# 8_button_harvester.net
KiCad netlist of a schematic drawn in EAGLE
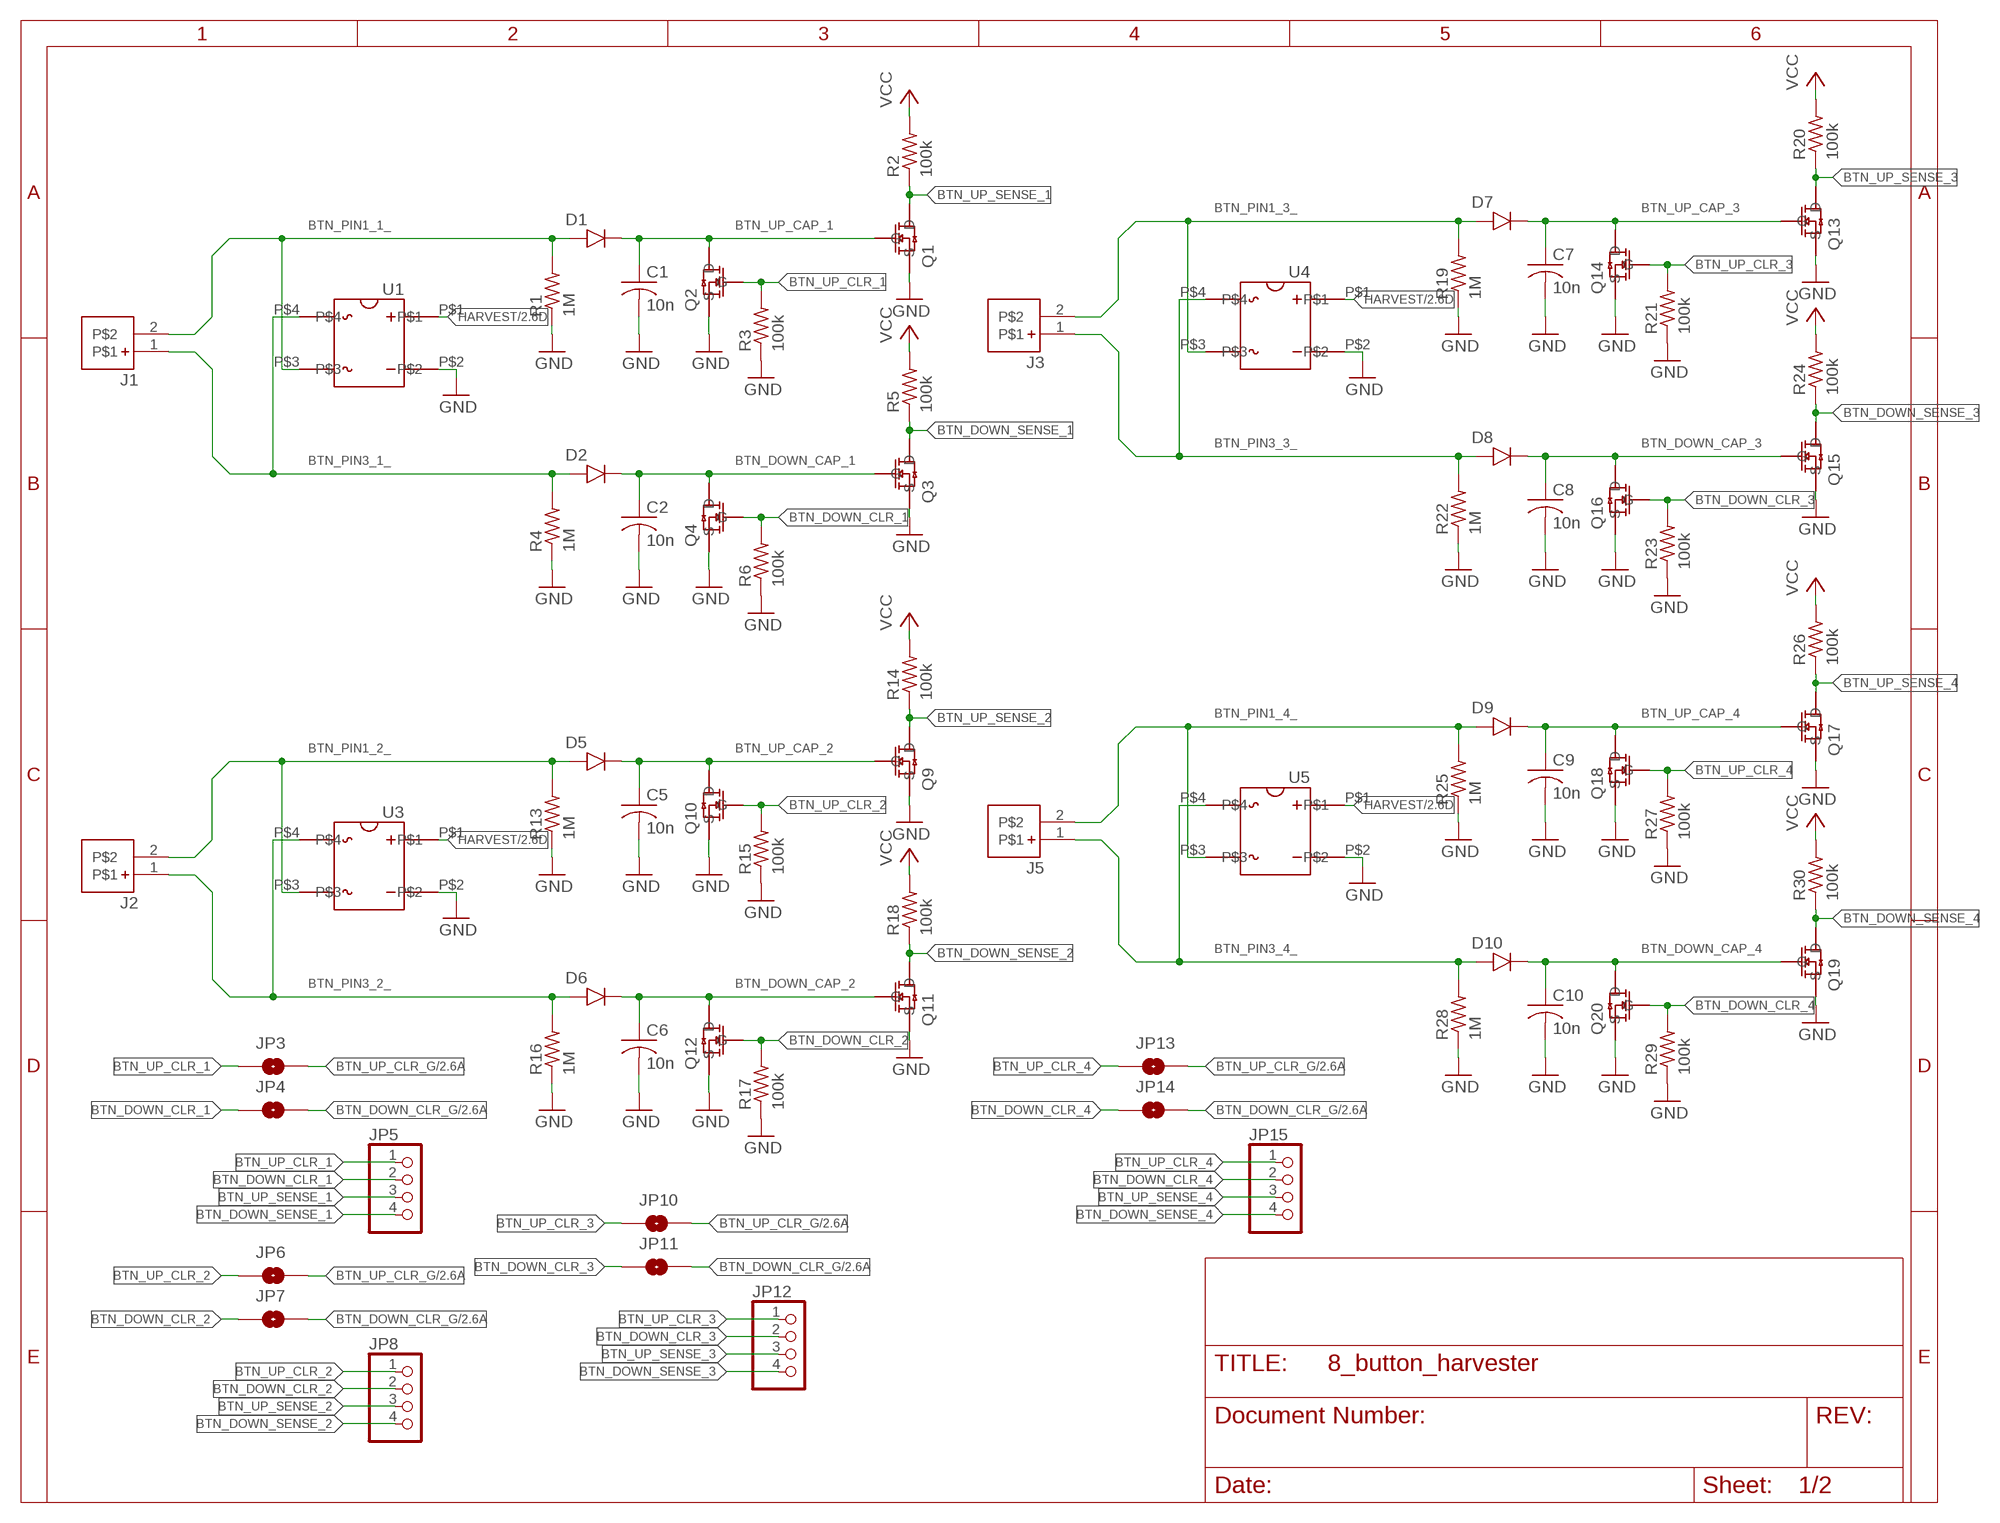
[diagram p0: schematic, sheet 1]
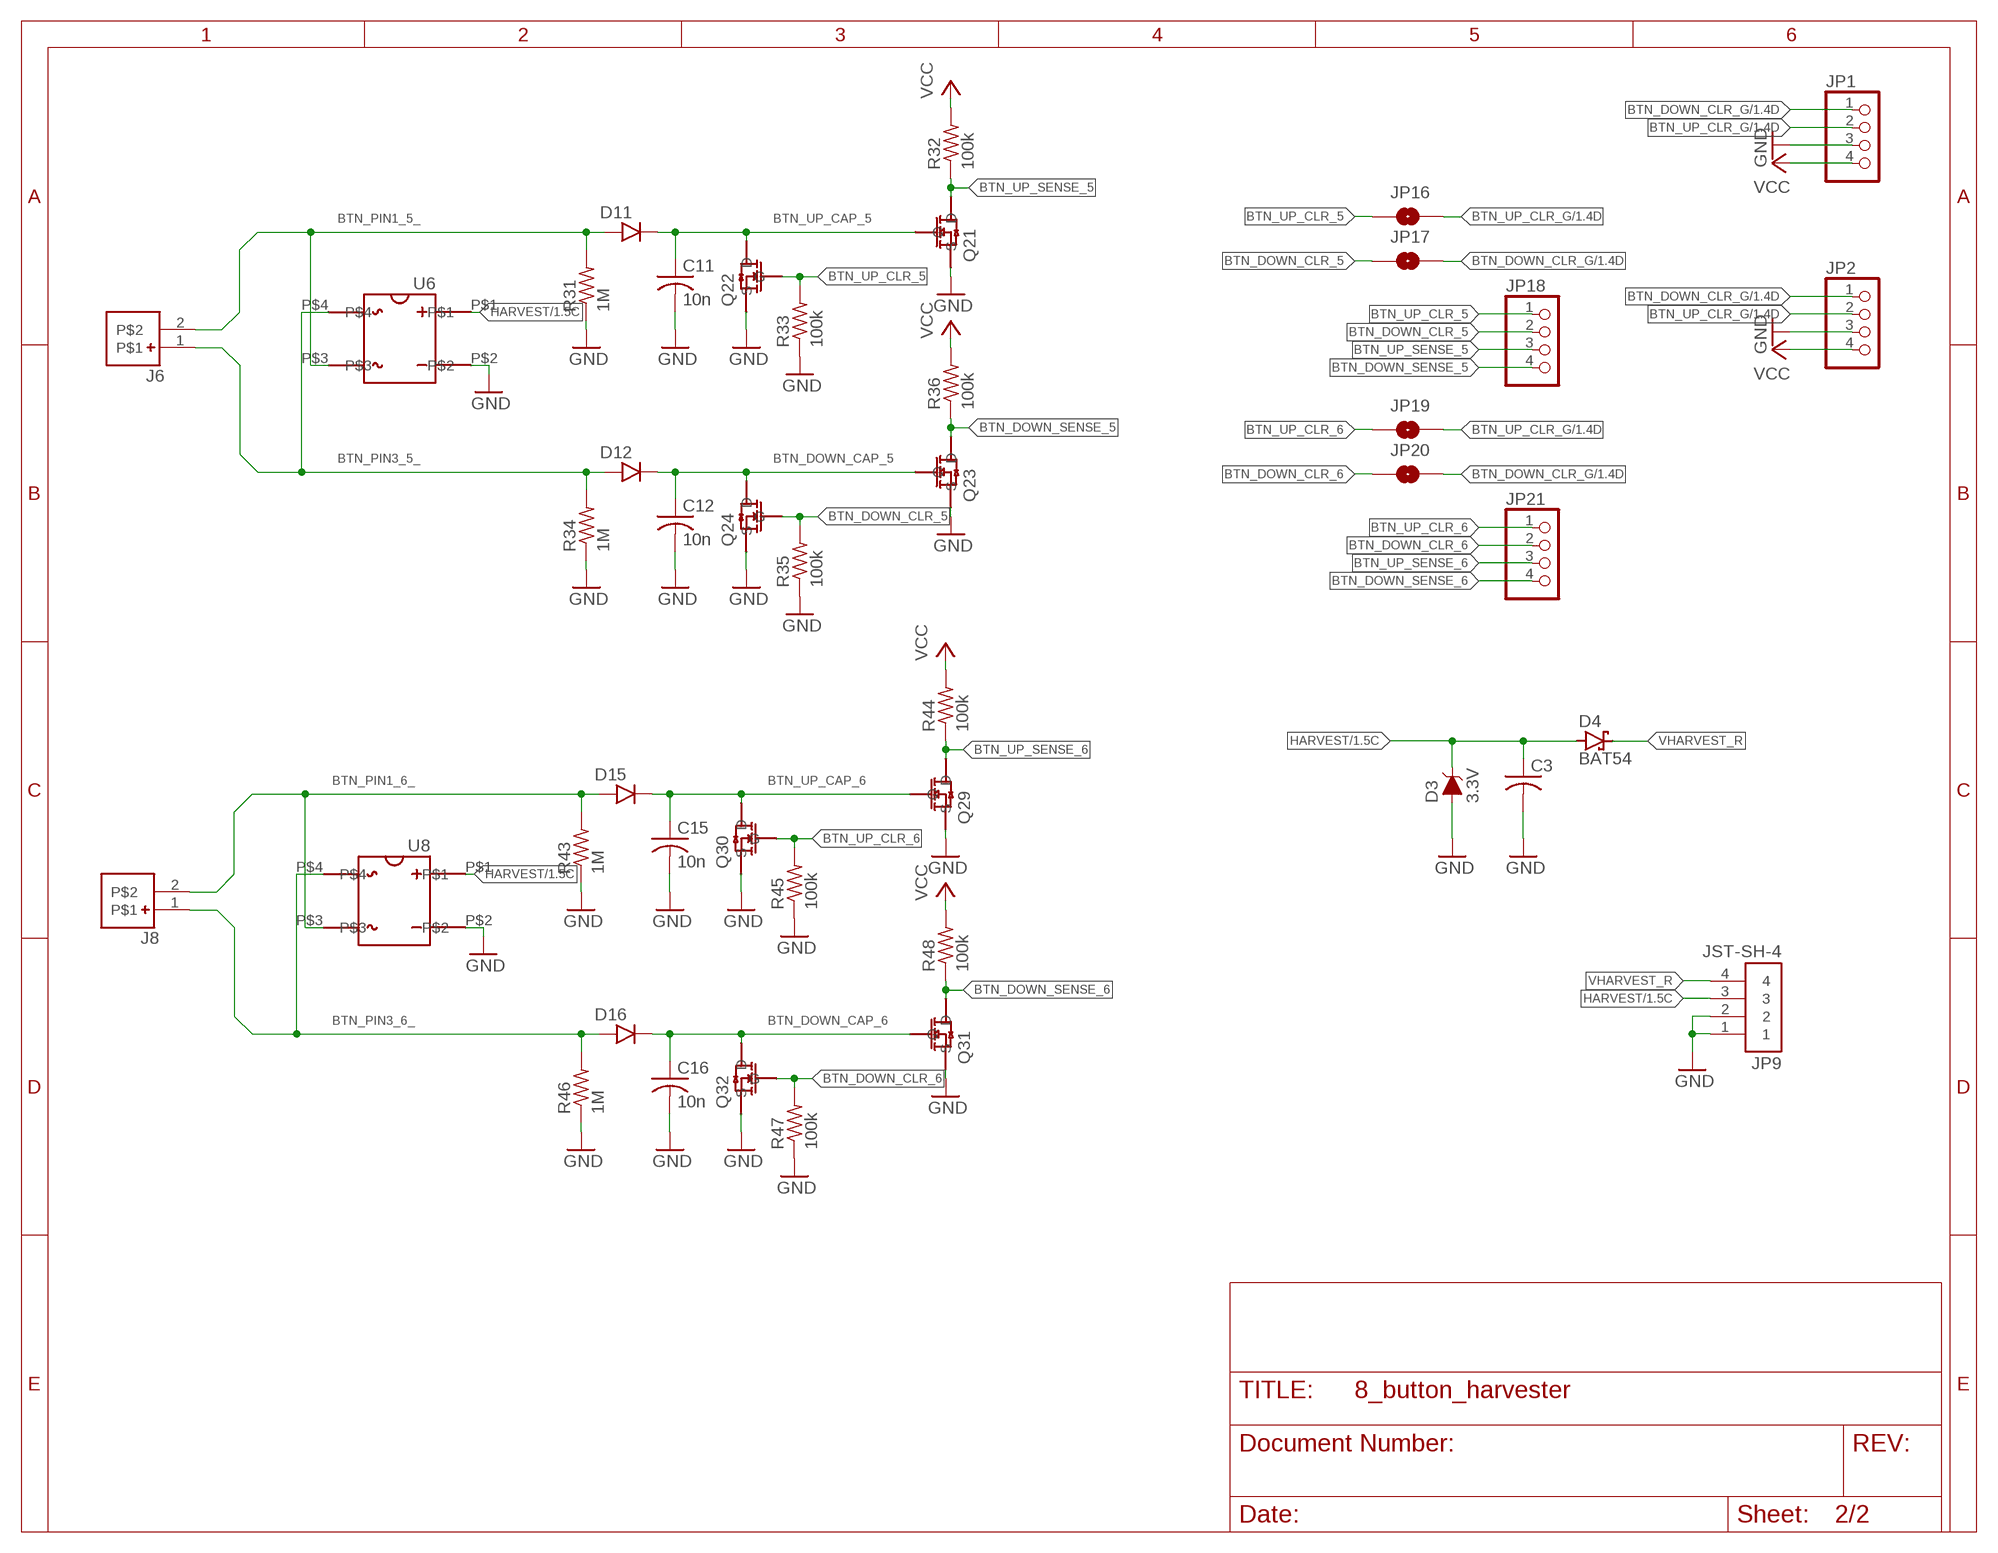
[diagram p1: schematic, sheet 2]

(export (version "E")
  (design (tool "Eeschema 10.0.6"))
  (components
    (comp (ref "C3")
      (value "C-USC0805")
      (footprint "eagle-import:C0805")
      (libsource (lib "eagle-import") (part "C-USC0805"))
    )
    (comp (ref "C11")
      (value "10n")
      (footprint "eagle-import:C0402")
      (libsource (lib "eagle-import") (part "C-USC0402"))
    )
    (comp (ref "C12")
      (value "10n")
      (footprint "eagle-import:C0402")
      (libsource (lib "eagle-import") (part "C-USC0402"))
    )
    (comp (ref "C15")
      (value "10n")
      (footprint "eagle-import:C0402")
      (libsource (lib "eagle-import") (part "C-USC0402"))
    )
    (comp (ref "C16")
      (value "10n")
      (footprint "eagle-import:C0402")
      (libsource (lib "eagle-import") (part "C-USC0402"))
    )
    (comp (ref "D3")
      (value "3.3V")
      (footprint "eagle-import:SOD-323")
      (libsource (lib "eagle-import") (part "DIODE-ZENER-MM3Z3V3T1G"))
    )
    (comp (ref "D4")
      (value "BAT54")
      (footprint "eagle-import:SOT23")
      (libsource (lib "eagle-import") (part "BAT54"))
    )
    (comp (ref "D11")
      (value "DFLU1200")
      (footprint "eagle-import:DFLU1200")
      (libsource (lib "eagle-import") (part "DFLU1200"))
    )
    (comp (ref "D12")
      (value "DFLU1200")
      (footprint "eagle-import:DFLU1200")
      (libsource (lib "eagle-import") (part "DFLU1200"))
    )
    (comp (ref "D15")
      (value "DFLU1200")
      (footprint "eagle-import:DFLU1200")
      (libsource (lib "eagle-import") (part "DFLU1200"))
    )
    (comp (ref "D16")
      (value "DFLU1200")
      (footprint "eagle-import:DFLU1200")
      (libsource (lib "eagle-import") (part "DFLU1200"))
    )
    (comp (ref "J6")
      (value "S2B-PH-SM4-TB")
      (footprint "eagle-import:S2B-PH-SM4-TB")
      (libsource (lib "eagle-import") (part "S2B-PH-SM4-TB"))
    )
    (comp (ref "J8")
      (value "S2B-PH-SM4-TB")
      (footprint "eagle-import:S2B-PH-SM4-TB")
      (libsource (lib "eagle-import") (part "S2B-PH-SM4-TB"))
    )
    (comp (ref "JP1")
      (value "PINHD-1X4")
      (footprint "eagle-import:1X04")
      (libsource (lib "eagle-import") (part "PINHD-1X4"))
    )
    (comp (ref "JP2")
      (value "PINHD-1X4")
      (footprint "eagle-import:1X04")
      (libsource (lib "eagle-import") (part "PINHD-1X4"))
    )
    (comp (ref "JP9")
      (value "JST-SH-4")
      (footprint "eagle-import:JST-SH-4")
      (libsource (lib "eagle-import") (part "JST-SH-4"))
    )
    (comp (ref "JP16")
      (value "JUMPER-SMT_2_NO_NO-SILK")
      (footprint "eagle-import:SMT-JUMPER_2_NO_NO-SILK")
      (libsource (lib "eagle-import") (part "JUMPER-SMT_2_NO_NO-SILK"))
    )
    (comp (ref "JP17")
      (value "JUMPER-SMT_2_NO_NO-SILK")
      (footprint "eagle-import:SMT-JUMPER_2_NO_NO-SILK")
      (libsource (lib "eagle-import") (part "JUMPER-SMT_2_NO_NO-SILK"))
    )
    (comp (ref "JP18")
      (value "PINHD-1X4")
      (footprint "eagle-import:1X04")
      (libsource (lib "eagle-import") (part "PINHD-1X4"))
    )
    (comp (ref "JP19")
      (value "JUMPER-SMT_2_NO_NO-SILK")
      (footprint "eagle-import:SMT-JUMPER_2_NO_NO-SILK")
      (libsource (lib "eagle-import") (part "JUMPER-SMT_2_NO_NO-SILK"))
    )
    (comp (ref "JP20")
      (value "JUMPER-SMT_2_NO_NO-SILK")
      (footprint "eagle-import:SMT-JUMPER_2_NO_NO-SILK")
      (libsource (lib "eagle-import") (part "JUMPER-SMT_2_NO_NO-SILK"))
    )
    (comp (ref "JP21")
      (value "PINHD-1X4")
      (footprint "eagle-import:1X04")
      (libsource (lib "eagle-import") (part "PINHD-1X4"))
    )
    (comp (ref "Q21")
      (value "2N7002K-7")
      (footprint "eagle-import:2N7002K-7")
      (libsource (lib "eagle-import") (part "2N7002K-7"))
    )
    (comp (ref "Q22")
      (value "BSS138K")
      (footprint "eagle-import:BSS138K")
      (libsource (lib "eagle-import") (part "BSS138K"))
    )
    (comp (ref "Q23")
      (value "2N7002K-7")
      (footprint "eagle-import:2N7002K-7")
      (libsource (lib "eagle-import") (part "2N7002K-7"))
    )
    (comp (ref "Q24")
      (value "BSS138K")
      (footprint "eagle-import:BSS138K")
      (libsource (lib "eagle-import") (part "BSS138K"))
    )
    (comp (ref "Q29")
      (value "2N7002K-7")
      (footprint "eagle-import:2N7002K-7")
      (libsource (lib "eagle-import") (part "2N7002K-7"))
    )
    (comp (ref "Q30")
      (value "BSS138K")
      (footprint "eagle-import:BSS138K")
      (libsource (lib "eagle-import") (part "BSS138K"))
    )
    (comp (ref "Q31")
      (value "2N7002K-7")
      (footprint "eagle-import:2N7002K-7")
      (libsource (lib "eagle-import") (part "2N7002K-7"))
    )
    (comp (ref "Q32")
      (value "BSS138K")
      (footprint "eagle-import:BSS138K")
      (libsource (lib "eagle-import") (part "BSS138K"))
    )
    (comp (ref "R31")
      (value "1M")
      (footprint "eagle-import:R0402")
      (libsource (lib "eagle-import") (part "R-US_R0402"))
    )
    (comp (ref "R32")
      (value "100k")
      (footprint "eagle-import:R0402")
      (libsource (lib "eagle-import") (part "R-US_R0402"))
    )
    (comp (ref "R33")
      (value "100k")
      (footprint "eagle-import:R0402")
      (libsource (lib "eagle-import") (part "R-US_R0402"))
    )
    (comp (ref "R34")
      (value "1M")
      (footprint "eagle-import:R0402")
      (libsource (lib "eagle-import") (part "R-US_R0402"))
    )
    (comp (ref "R35")
      (value "100k")
      (footprint "eagle-import:R0402")
      (libsource (lib "eagle-import") (part "R-US_R0402"))
    )
    (comp (ref "R36")
      (value "100k")
      (footprint "eagle-import:R0402")
      (libsource (lib "eagle-import") (part "R-US_R0402"))
    )
    (comp (ref "R43")
      (value "1M")
      (footprint "eagle-import:R0402")
      (libsource (lib "eagle-import") (part "R-US_R0402"))
    )
    (comp (ref "R44")
      (value "100k")
      (footprint "eagle-import:R0402")
      (libsource (lib "eagle-import") (part "R-US_R0402"))
    )
    (comp (ref "R45")
      (value "100k")
      (footprint "eagle-import:R0402")
      (libsource (lib "eagle-import") (part "R-US_R0402"))
    )
    (comp (ref "R46")
      (value "1M")
      (footprint "eagle-import:R0402")
      (libsource (lib "eagle-import") (part "R-US_R0402"))
    )
    (comp (ref "R47")
      (value "100k")
      (footprint "eagle-import:R0402")
      (libsource (lib "eagle-import") (part "R-US_R0402"))
    )
    (comp (ref "R48")
      (value "100k")
      (footprint "eagle-import:R0402")
      (libsource (lib "eagle-import") (part "R-US_R0402"))
    )
    (comp (ref "U6")
      (value "CDBHD140L-G")
      (footprint "eagle-import:CDBHDXX0L-G")
      (libsource (lib "eagle-import") (part "CDBHD140L-G"))
    )
    (comp (ref "U8")
      (value "CDBHD140L-G")
      (footprint "eagle-import:CDBHDXX0L-G")
      (libsource (lib "eagle-import") (part "CDBHD140L-G"))
    )
    (comp (ref "C1")
      (value "10n")
      (footprint "eagle-import:C0402")
      (libsource (lib "eagle-import") (part "C-USC0402"))
    )
    (comp (ref "C2")
      (value "10n")
      (footprint "eagle-import:C0402")
      (libsource (lib "eagle-import") (part "C-USC0402"))
    )
    (comp (ref "C5")
      (value "10n")
      (footprint "eagle-import:C0402")
      (libsource (lib "eagle-import") (part "C-USC0402"))
    )
    (comp (ref "C6")
      (value "10n")
      (footprint "eagle-import:C0402")
      (libsource (lib "eagle-import") (part "C-USC0402"))
    )
    (comp (ref "C7")
      (value "10n")
      (footprint "eagle-import:C0402")
      (libsource (lib "eagle-import") (part "C-USC0402"))
    )
    (comp (ref "C8")
      (value "10n")
      (footprint "eagle-import:C0402")
      (libsource (lib "eagle-import") (part "C-USC0402"))
    )
    (comp (ref "C9")
      (value "10n")
      (footprint "eagle-import:C0402")
      (libsource (lib "eagle-import") (part "C-USC0402"))
    )
    (comp (ref "C10")
      (value "10n")
      (footprint "eagle-import:C0402")
      (libsource (lib "eagle-import") (part "C-USC0402"))
    )
    (comp (ref "D1")
      (value "DFLU1200")
      (footprint "eagle-import:DFLU1200")
      (libsource (lib "eagle-import") (part "DFLU1200"))
    )
    (comp (ref "D2")
      (value "DFLU1200")
      (footprint "eagle-import:DFLU1200")
      (libsource (lib "eagle-import") (part "DFLU1200"))
    )
    (comp (ref "D5")
      (value "DFLU1200")
      (footprint "eagle-import:DFLU1200")
      (libsource (lib "eagle-import") (part "DFLU1200"))
    )
    (comp (ref "D6")
      (value "DFLU1200")
      (footprint "eagle-import:DFLU1200")
      (libsource (lib "eagle-import") (part "DFLU1200"))
    )
    (comp (ref "D7")
      (value "DFLU1200")
      (footprint "eagle-import:DFLU1200")
      (libsource (lib "eagle-import") (part "DFLU1200"))
    )
    (comp (ref "D8")
      (value "DFLU1200")
      (footprint "eagle-import:DFLU1200")
      (libsource (lib "eagle-import") (part "DFLU1200"))
    )
    (comp (ref "D9")
      (value "DFLU1200")
      (footprint "eagle-import:DFLU1200")
      (libsource (lib "eagle-import") (part "DFLU1200"))
    )
    (comp (ref "D10")
      (value "DFLU1200")
      (footprint "eagle-import:DFLU1200")
      (libsource (lib "eagle-import") (part "DFLU1200"))
    )
    (comp (ref "J1")
      (value "S2B-PH-SM4-TB")
      (footprint "eagle-import:S2B-PH-SM4-TB")
      (libsource (lib "eagle-import") (part "S2B-PH-SM4-TB"))
    )
    (comp (ref "J2")
      (value "S2B-PH-SM4-TB")
      (footprint "eagle-import:S2B-PH-SM4-TB")
      (libsource (lib "eagle-import") (part "S2B-PH-SM4-TB"))
    )
    (comp (ref "J3")
      (value "S2B-PH-SM4-TB")
      (footprint "eagle-import:S2B-PH-SM4-TB")
      (libsource (lib "eagle-import") (part "S2B-PH-SM4-TB"))
    )
    (comp (ref "J5")
      (value "S2B-PH-SM4-TB")
      (footprint "eagle-import:S2B-PH-SM4-TB")
      (libsource (lib "eagle-import") (part "S2B-PH-SM4-TB"))
    )
    (comp (ref "JP3")
      (value "JUMPER-SMT_2_NO_NO-SILK")
      (footprint "eagle-import:SMT-JUMPER_2_NO_NO-SILK")
      (libsource (lib "eagle-import") (part "JUMPER-SMT_2_NO_NO-SILK"))
    )
    (comp (ref "JP4")
      (value "JUMPER-SMT_2_NO_NO-SILK")
      (footprint "eagle-import:SMT-JUMPER_2_NO_NO-SILK")
      (libsource (lib "eagle-import") (part "JUMPER-SMT_2_NO_NO-SILK"))
    )
    (comp (ref "JP5")
      (value "PINHD-1X4")
      (footprint "eagle-import:1X04")
      (libsource (lib "eagle-import") (part "PINHD-1X4"))
    )
    (comp (ref "JP6")
      (value "JUMPER-SMT_2_NO_NO-SILK")
      (footprint "eagle-import:SMT-JUMPER_2_NO_NO-SILK")
      (libsource (lib "eagle-import") (part "JUMPER-SMT_2_NO_NO-SILK"))
    )
    (comp (ref "JP7")
      (value "JUMPER-SMT_2_NO_NO-SILK")
      (footprint "eagle-import:SMT-JUMPER_2_NO_NO-SILK")
      (libsource (lib "eagle-import") (part "JUMPER-SMT_2_NO_NO-SILK"))
    )
    (comp (ref "JP8")
      (value "PINHD-1X4")
      (footprint "eagle-import:1X04")
      (libsource (lib "eagle-import") (part "PINHD-1X4"))
    )
    (comp (ref "JP10")
      (value "JUMPER-SMT_2_NO_NO-SILK")
      (footprint "eagle-import:SMT-JUMPER_2_NO_NO-SILK")
      (libsource (lib "eagle-import") (part "JUMPER-SMT_2_NO_NO-SILK"))
    )
    (comp (ref "JP11")
      (value "JUMPER-SMT_2_NO_NO-SILK")
      (footprint "eagle-import:SMT-JUMPER_2_NO_NO-SILK")
      (libsource (lib "eagle-import") (part "JUMPER-SMT_2_NO_NO-SILK"))
    )
    (comp (ref "JP12")
      (value "PINHD-1X4")
      (footprint "eagle-import:1X04")
      (libsource (lib "eagle-import") (part "PINHD-1X4"))
    )
    (comp (ref "JP13")
      (value "JUMPER-SMT_2_NO_NO-SILK")
      (footprint "eagle-import:SMT-JUMPER_2_NO_NO-SILK")
      (libsource (lib "eagle-import") (part "JUMPER-SMT_2_NO_NO-SILK"))
    )
    (comp (ref "JP14")
      (value "JUMPER-SMT_2_NO_NO-SILK")
      (footprint "eagle-import:SMT-JUMPER_2_NO_NO-SILK")
      (libsource (lib "eagle-import") (part "JUMPER-SMT_2_NO_NO-SILK"))
    )
    (comp (ref "JP15")
      (value "PINHD-1X4")
      (footprint "eagle-import:1X04")
      (libsource (lib "eagle-import") (part "PINHD-1X4"))
    )
    (comp (ref "Q1")
      (value "2N7002K-7")
      (footprint "eagle-import:2N7002K-7")
      (libsource (lib "eagle-import") (part "2N7002K-7"))
    )
    (comp (ref "Q2")
      (value "BSS138K")
      (footprint "eagle-import:BSS138K")
      (libsource (lib "eagle-import") (part "BSS138K"))
    )
    (comp (ref "Q3")
      (value "2N7002K-7")
      (footprint "eagle-import:2N7002K-7")
      (libsource (lib "eagle-import") (part "2N7002K-7"))
    )
    (comp (ref "Q4")
      (value "BSS138K")
      (footprint "eagle-import:BSS138K")
      (libsource (lib "eagle-import") (part "BSS138K"))
    )
    (comp (ref "Q9")
      (value "2N7002K-7")
      (footprint "eagle-import:2N7002K-7")
      (libsource (lib "eagle-import") (part "2N7002K-7"))
    )
    (comp (ref "Q10")
      (value "BSS138K")
      (footprint "eagle-import:BSS138K")
      (libsource (lib "eagle-import") (part "BSS138K"))
    )
    (comp (ref "Q11")
      (value "2N7002K-7")
      (footprint "eagle-import:2N7002K-7")
      (libsource (lib "eagle-import") (part "2N7002K-7"))
    )
    (comp (ref "Q12")
      (value "BSS138K")
      (footprint "eagle-import:BSS138K")
      (libsource (lib "eagle-import") (part "BSS138K"))
    )
    (comp (ref "Q13")
      (value "2N7002K-7")
      (footprint "eagle-import:2N7002K-7")
      (libsource (lib "eagle-import") (part "2N7002K-7"))
    )
    (comp (ref "Q14")
      (value "BSS138K")
      (footprint "eagle-import:BSS138K")
      (libsource (lib "eagle-import") (part "BSS138K"))
    )
    (comp (ref "Q15")
      (value "2N7002K-7")
      (footprint "eagle-import:2N7002K-7")
      (libsource (lib "eagle-import") (part "2N7002K-7"))
    )
    (comp (ref "Q16")
      (value "BSS138K")
      (footprint "eagle-import:BSS138K")
      (libsource (lib "eagle-import") (part "BSS138K"))
    )
    (comp (ref "Q17")
      (value "2N7002K-7")
      (footprint "eagle-import:2N7002K-7")
      (libsource (lib "eagle-import") (part "2N7002K-7"))
    )
    (comp (ref "Q18")
      (value "BSS138K")
      (footprint "eagle-import:BSS138K")
      (libsource (lib "eagle-import") (part "BSS138K"))
    )
    (comp (ref "Q19")
      (value "2N7002K-7")
      (footprint "eagle-import:2N7002K-7")
      (libsource (lib "eagle-import") (part "2N7002K-7"))
    )
    (comp (ref "Q20")
      (value "BSS138K")
      (footprint "eagle-import:BSS138K")
      (libsource (lib "eagle-import") (part "BSS138K"))
    )
    (comp (ref "R1")
      (value "1M")
      (footprint "eagle-import:R0402")
      (libsource (lib "eagle-import") (part "R-US_R0402"))
    )
    (comp (ref "R2")
      (value "100k")
      (footprint "eagle-import:R0402")
      (libsource (lib "eagle-import") (part "R-US_R0402"))
    )
    (comp (ref "R3")
      (value "100k")
      (footprint "eagle-import:R0402")
      (libsource (lib "eagle-import") (part "R-US_R0402"))
    )
    (comp (ref "R4")
      (value "1M")
      (footprint "eagle-import:R0402")
      (libsource (lib "eagle-import") (part "R-US_R0402"))
    )
    (comp (ref "R5")
      (value "100k")
      (footprint "eagle-import:R0402")
      (libsource (lib "eagle-import") (part "R-US_R0402"))
    )
    (comp (ref "R6")
      (value "100k")
      (footprint "eagle-import:R0402")
      (libsource (lib "eagle-import") (part "R-US_R0402"))
    )
    (comp (ref "R13")
      (value "1M")
      (footprint "eagle-import:R0402")
      (libsource (lib "eagle-import") (part "R-US_R0402"))
    )
    (comp (ref "R14")
      (value "100k")
      (footprint "eagle-import:R0402")
      (libsource (lib "eagle-import") (part "R-US_R0402"))
    )
    (comp (ref "R15")
      (value "100k")
      (footprint "eagle-import:R0402")
      (libsource (lib "eagle-import") (part "R-US_R0402"))
    )
    (comp (ref "R16")
      (value "1M")
      (footprint "eagle-import:R0402")
      (libsource (lib "eagle-import") (part "R-US_R0402"))
    )
    (comp (ref "R17")
      (value "100k")
      (footprint "eagle-import:R0402")
      (libsource (lib "eagle-import") (part "R-US_R0402"))
    )
    (comp (ref "R18")
      (value "100k")
      (footprint "eagle-import:R0402")
      (libsource (lib "eagle-import") (part "R-US_R0402"))
    )
    (comp (ref "R19")
      (value "1M")
      (footprint "eagle-import:R0402")
      (libsource (lib "eagle-import") (part "R-US_R0402"))
    )
    (comp (ref "R20")
      (value "100k")
      (footprint "eagle-import:R0402")
      (libsource (lib "eagle-import") (part "R-US_R0402"))
    )
    (comp (ref "R21")
      (value "100k")
      (footprint "eagle-import:R0402")
      (libsource (lib "eagle-import") (part "R-US_R0402"))
    )
    (comp (ref "R22")
      (value "1M")
      (footprint "eagle-import:R0402")
      (libsource (lib "eagle-import") (part "R-US_R0402"))
    )
    (comp (ref "R23")
      (value "100k")
      (footprint "eagle-import:R0402")
      (libsource (lib "eagle-import") (part "R-US_R0402"))
    )
    (comp (ref "R24")
      (value "100k")
      (footprint "eagle-import:R0402")
      (libsource (lib "eagle-import") (part "R-US_R0402"))
    )
    (comp (ref "R25")
      (value "1M")
      (footprint "eagle-import:R0402")
      (libsource (lib "eagle-import") (part "R-US_R0402"))
    )
    (comp (ref "R26")
      (value "100k")
      (footprint "eagle-import:R0402")
      (libsource (lib "eagle-import") (part "R-US_R0402"))
    )
    (comp (ref "R27")
      (value "100k")
      (footprint "eagle-import:R0402")
      (libsource (lib "eagle-import") (part "R-US_R0402"))
    )
    (comp (ref "R28")
      (value "1M")
      (footprint "eagle-import:R0402")
      (libsource (lib "eagle-import") (part "R-US_R0402"))
    )
    (comp (ref "R29")
      (value "100k")
      (footprint "eagle-import:R0402")
      (libsource (lib "eagle-import") (part "R-US_R0402"))
    )
    (comp (ref "R30")
      (value "100k")
      (footprint "eagle-import:R0402")
      (libsource (lib "eagle-import") (part "R-US_R0402"))
    )
    (comp (ref "U1")
      (value "CDBHD140L-G")
      (footprint "eagle-import:CDBHDXX0L-G")
      (libsource (lib "eagle-import") (part "CDBHD140L-G"))
    )
    (comp (ref "U3")
      (value "CDBHD140L-G")
      (footprint "eagle-import:CDBHDXX0L-G")
      (libsource (lib "eagle-import") (part "CDBHD140L-G"))
    )
    (comp (ref "U4")
      (value "CDBHD140L-G")
      (footprint "eagle-import:CDBHDXX0L-G")
      (libsource (lib "eagle-import") (part "CDBHD140L-G"))
    )
    (comp (ref "U5")
      (value "CDBHD140L-G")
      (footprint "eagle-import:CDBHDXX0L-G")
      (libsource (lib "eagle-import") (part "CDBHD140L-G"))
    )
  )
  (nets
    (net (code "1") (name "BTN_DOWN_CAP_1") (class "Default")
      (node (ref "C2") (pin "1") (pinfunction "1_1") (pintype "passive"))
      (node (ref "D2") (pin "K") (pinfunction "K_K") (pintype "bidirectional"))
      (node (ref "Q3") (pin "G") (pinfunction "G_G") (pintype "bidirectional"))
      (node (ref "Q4") (pin "D") (pinfunction "D_D") (pintype "bidirectional"))
    )
    (net (code "2") (name "BTN_DOWN_CAP_2") (class "Default")
      (node (ref "C6") (pin "1") (pinfunction "1_1") (pintype "passive"))
      (node (ref "D6") (pin "K") (pinfunction "K_K") (pintype "bidirectional"))
      (node (ref "Q11") (pin "G") (pinfunction "G_G") (pintype "bidirectional"))
      (node (ref "Q12") (pin "D") (pinfunction "D_D") (pintype "bidirectional"))
    )
    (net (code "3") (name "BTN_DOWN_CAP_3") (class "Default")
      (node (ref "C8") (pin "1") (pinfunction "1_1") (pintype "passive"))
      (node (ref "D8") (pin "K") (pinfunction "K_K") (pintype "bidirectional"))
      (node (ref "Q15") (pin "G") (pinfunction "G_G") (pintype "bidirectional"))
      (node (ref "Q16") (pin "D") (pinfunction "D_D") (pintype "bidirectional"))
    )
    (net (code "4") (name "BTN_DOWN_CAP_4") (class "Default")
      (node (ref "C10") (pin "1") (pinfunction "1_1") (pintype "passive"))
      (node (ref "D10") (pin "K") (pinfunction "K_K") (pintype "bidirectional"))
      (node (ref "Q19") (pin "G") (pinfunction "G_G") (pintype "bidirectional"))
      (node (ref "Q20") (pin "D") (pinfunction "D_D") (pintype "bidirectional"))
    )
    (net (code "5") (name "BTN_DOWN_CAP_5") (class "Default")
      (node (ref "C12") (pin "1") (pinfunction "1_1") (pintype "passive"))
      (node (ref "D12") (pin "K") (pinfunction "K_K") (pintype "bidirectional"))
      (node (ref "Q23") (pin "G") (pinfunction "G_G") (pintype "bidirectional"))
      (node (ref "Q24") (pin "D") (pinfunction "D_D") (pintype "bidirectional"))
    )
    (net (code "6") (name "BTN_DOWN_CAP_6") (class "Default")
      (node (ref "C16") (pin "1") (pinfunction "1_1") (pintype "passive"))
      (node (ref "D16") (pin "K") (pinfunction "K_K") (pintype "bidirectional"))
      (node (ref "Q31") (pin "G") (pinfunction "G_G") (pintype "bidirectional"))
      (node (ref "Q32") (pin "D") (pinfunction "D_D") (pintype "bidirectional"))
    )
    (net (code "7") (name "BTN_DOWN_CLR_1") (class "Default")
      (node (ref "JP4") (pin "1") (pinfunction "1_1") (pintype "passive"))
      (node (ref "JP5") (pin "2") (pinfunction "2_2") (pintype "passive"))
      (node (ref "Q4") (pin "G") (pinfunction "G_G") (pintype "bidirectional"))
      (node (ref "R6") (pin "2") (pinfunction "2_2") (pintype "passive"))
    )
    (net (code "8") (name "BTN_DOWN_CLR_2") (class "Default")
      (node (ref "JP7") (pin "1") (pinfunction "1_1") (pintype "passive"))
      (node (ref "JP8") (pin "2") (pinfunction "2_2") (pintype "passive"))
      (node (ref "Q12") (pin "G") (pinfunction "G_G") (pintype "bidirectional"))
      (node (ref "R17") (pin "2") (pinfunction "2_2") (pintype "passive"))
    )
    (net (code "9") (name "BTN_DOWN_CLR_3") (class "Default")
      (node (ref "JP11") (pin "1") (pinfunction "1_1") (pintype "passive"))
      (node (ref "JP12") (pin "2") (pinfunction "2_2") (pintype "passive"))
      (node (ref "Q16") (pin "G") (pinfunction "G_G") (pintype "bidirectional"))
      (node (ref "R23") (pin "2") (pinfunction "2_2") (pintype "passive"))
    )
    (net (code "10") (name "BTN_DOWN_CLR_4") (class "Default")
      (node (ref "JP14") (pin "1") (pinfunction "1_1") (pintype "passive"))
      (node (ref "JP15") (pin "2") (pinfunction "2_2") (pintype "passive"))
      (node (ref "Q20") (pin "G") (pinfunction "G_G") (pintype "bidirectional"))
      (node (ref "R29") (pin "2") (pinfunction "2_2") (pintype "passive"))
    )
    (net (code "11") (name "BTN_DOWN_CLR_5") (class "Default")
      (node (ref "JP17") (pin "1") (pinfunction "1_1") (pintype "passive"))
      (node (ref "JP18") (pin "2") (pinfunction "2_2") (pintype "passive"))
      (node (ref "Q24") (pin "G") (pinfunction "G_G") (pintype "bidirectional"))
      (node (ref "R35") (pin "2") (pinfunction "2_2") (pintype "passive"))
    )
    (net (code "12") (name "BTN_DOWN_CLR_6") (class "Default")
      (node (ref "JP20") (pin "1") (pinfunction "1_1") (pintype "passive"))
      (node (ref "JP21") (pin "2") (pinfunction "2_2") (pintype "passive"))
      (node (ref "Q32") (pin "G") (pinfunction "G_G") (pintype "bidirectional"))
      (node (ref "R47") (pin "2") (pinfunction "2_2") (pintype "passive"))
    )
    (net (code "13") (name "BTN_DOWN_CLR_G") (class "Default")
      (node (ref "JP1") (pin "1") (pinfunction "1_1") (pintype "passive"))
      (node (ref "JP11") (pin "2") (pinfunction "2_2") (pintype "passive"))
      (node (ref "JP14") (pin "2") (pinfunction "2_2") (pintype "passive"))
      (node (ref "JP17") (pin "2") (pinfunction "2_2") (pintype "passive"))
      (node (ref "JP2") (pin "1") (pinfunction "1_1") (pintype "passive"))
      (node (ref "JP20") (pin "2") (pinfunction "2_2") (pintype "passive"))
      (node (ref "JP4") (pin "2") (pinfunction "2_2") (pintype "passive"))
      (node (ref "JP7") (pin "2") (pinfunction "2_2") (pintype "passive"))
    )
    (net (code "14") (name "BTN_DOWN_SENSE_1") (class "Default")
      (node (ref "JP5") (pin "4") (pinfunction "4_4") (pintype "passive"))
      (node (ref "Q3") (pin "D") (pinfunction "D_D") (pintype "bidirectional"))
      (node (ref "R5") (pin "1") (pinfunction "1_1") (pintype "passive"))
    )
    (net (code "15") (name "BTN_DOWN_SENSE_2") (class "Default")
      (node (ref "JP8") (pin "4") (pinfunction "4_4") (pintype "passive"))
      (node (ref "Q11") (pin "D") (pinfunction "D_D") (pintype "bidirectional"))
      (node (ref "R18") (pin "1") (pinfunction "1_1") (pintype "passive"))
    )
    (net (code "16") (name "BTN_DOWN_SENSE_3") (class "Default")
      (node (ref "JP12") (pin "4") (pinfunction "4_4") (pintype "passive"))
      (node (ref "Q15") (pin "D") (pinfunction "D_D") (pintype "bidirectional"))
      (node (ref "R24") (pin "1") (pinfunction "1_1") (pintype "passive"))
    )
    (net (code "17") (name "BTN_DOWN_SENSE_4") (class "Default")
      (node (ref "JP15") (pin "4") (pinfunction "4_4") (pintype "passive"))
      (node (ref "Q19") (pin "D") (pinfunction "D_D") (pintype "bidirectional"))
      (node (ref "R30") (pin "1") (pinfunction "1_1") (pintype "passive"))
    )
    (net (code "18") (name "BTN_DOWN_SENSE_5") (class "Default")
      (node (ref "JP18") (pin "4") (pinfunction "4_4") (pintype "passive"))
      (node (ref "Q23") (pin "D") (pinfunction "D_D") (pintype "bidirectional"))
      (node (ref "R36") (pin "1") (pinfunction "1_1") (pintype "passive"))
    )
    (net (code "19") (name "BTN_DOWN_SENSE_6") (class "Default")
      (node (ref "JP21") (pin "4") (pinfunction "4_4") (pintype "passive"))
      (node (ref "Q31") (pin "D") (pinfunction "D_D") (pintype "bidirectional"))
      (node (ref "R48") (pin "1") (pinfunction "1_1") (pintype "passive"))
    )
    (net (code "20") (name "BTN_PIN1_1_") (class "Default")
      (node (ref "D1") (pin "A") (pinfunction "A_A") (pintype "bidirectional"))
      (node (ref "J1") (pin "2") (pinfunction "P$2_2") (pintype "bidirectional"))
      (node (ref "R1") (pin "2") (pinfunction "2_2") (pintype "passive"))
      (node (ref "U1") (pin "P$3") (pinfunction "P$3_P$3") (pintype "bidirectional"))
    )
    (net (code "21") (name "BTN_PIN1_2_") (class "Default")
      (node (ref "D5") (pin "A") (pinfunction "A_A") (pintype "bidirectional"))
      (node (ref "J2") (pin "2") (pinfunction "P$2_2") (pintype "bidirectional"))
      (node (ref "R13") (pin "2") (pinfunction "2_2") (pintype "passive"))
      (node (ref "U3") (pin "P$3") (pinfunction "P$3_P$3") (pintype "bidirectional"))
    )
    (net (code "22") (name "BTN_PIN1_3_") (class "Default")
      (node (ref "D7") (pin "A") (pinfunction "A_A") (pintype "bidirectional"))
      (node (ref "J3") (pin "2") (pinfunction "P$2_2") (pintype "bidirectional"))
      (node (ref "R19") (pin "2") (pinfunction "2_2") (pintype "passive"))
      (node (ref "U4") (pin "P$3") (pinfunction "P$3_P$3") (pintype "bidirectional"))
    )
    (net (code "23") (name "BTN_PIN1_4_") (class "Default")
      (node (ref "D9") (pin "A") (pinfunction "A_A") (pintype "bidirectional"))
      (node (ref "J5") (pin "2") (pinfunction "P$2_2") (pintype "bidirectional"))
      (node (ref "R25") (pin "2") (pinfunction "2_2") (pintype "passive"))
      (node (ref "U5") (pin "P$3") (pinfunction "P$3_P$3") (pintype "bidirectional"))
    )
    (net (code "24") (name "BTN_PIN1_5_") (class "Default")
      (node (ref "D11") (pin "A") (pinfunction "A_A") (pintype "bidirectional"))
      (node (ref "J6") (pin "2") (pinfunction "P$2_2") (pintype "bidirectional"))
      (node (ref "R31") (pin "2") (pinfunction "2_2") (pintype "passive"))
      (node (ref "U6") (pin "P$3") (pinfunction "P$3_P$3") (pintype "bidirectional"))
    )
    (net (code "25") (name "BTN_PIN1_6_") (class "Default")
      (node (ref "D15") (pin "A") (pinfunction "A_A") (pintype "bidirectional"))
      (node (ref "J8") (pin "2") (pinfunction "P$2_2") (pintype "bidirectional"))
      (node (ref "R43") (pin "2") (pinfunction "2_2") (pintype "passive"))
      (node (ref "U8") (pin "P$3") (pinfunction "P$3_P$3") (pintype "bidirectional"))
    )
    (net (code "26") (name "BTN_PIN3_1_") (class "Default")
      (node (ref "D2") (pin "A") (pinfunction "A_A") (pintype "bidirectional"))
      (node (ref "J1") (pin "1") (pinfunction "P$1_1") (pintype "bidirectional"))
      (node (ref "R4") (pin "2") (pinfunction "2_2") (pintype "passive"))
      (node (ref "U1") (pin "P$4") (pinfunction "P$4_P$4") (pintype "bidirectional"))
    )
    (net (code "27") (name "BTN_PIN3_2_") (class "Default")
      (node (ref "D6") (pin "A") (pinfunction "A_A") (pintype "bidirectional"))
      (node (ref "J2") (pin "1") (pinfunction "P$1_1") (pintype "bidirectional"))
      (node (ref "R16") (pin "2") (pinfunction "2_2") (pintype "passive"))
      (node (ref "U3") (pin "P$4") (pinfunction "P$4_P$4") (pintype "bidirectional"))
    )
    (net (code "28") (name "BTN_PIN3_3_") (class "Default")
      (node (ref "D8") (pin "A") (pinfunction "A_A") (pintype "bidirectional"))
      (node (ref "J3") (pin "1") (pinfunction "P$1_1") (pintype "bidirectional"))
      (node (ref "R22") (pin "2") (pinfunction "2_2") (pintype "passive"))
      (node (ref "U4") (pin "P$4") (pinfunction "P$4_P$4") (pintype "bidirectional"))
    )
    (net (code "29") (name "BTN_PIN3_4_") (class "Default")
      (node (ref "D10") (pin "A") (pinfunction "A_A") (pintype "bidirectional"))
      (node (ref "J5") (pin "1") (pinfunction "P$1_1") (pintype "bidirectional"))
      (node (ref "R28") (pin "2") (pinfunction "2_2") (pintype "passive"))
      (node (ref "U5") (pin "P$4") (pinfunction "P$4_P$4") (pintype "bidirectional"))
    )
    (net (code "30") (name "BTN_PIN3_5_") (class "Default")
      (node (ref "D12") (pin "A") (pinfunction "A_A") (pintype "bidirectional"))
      (node (ref "J6") (pin "1") (pinfunction "P$1_1") (pintype "bidirectional"))
      (node (ref "R34") (pin "2") (pinfunction "2_2") (pintype "passive"))
      (node (ref "U6") (pin "P$4") (pinfunction "P$4_P$4") (pintype "bidirectional"))
    )
    (net (code "31") (name "BTN_PIN3_6_") (class "Default")
      (node (ref "D16") (pin "A") (pinfunction "A_A") (pintype "bidirectional"))
      (node (ref "J8") (pin "1") (pinfunction "P$1_1") (pintype "bidirectional"))
      (node (ref "R46") (pin "2") (pinfunction "2_2") (pintype "passive"))
      (node (ref "U8") (pin "P$4") (pinfunction "P$4_P$4") (pintype "bidirectional"))
    )
    (net (code "32") (name "BTN_UP_CAP_1") (class "Default")
      (node (ref "C1") (pin "1") (pinfunction "1_1") (pintype "passive"))
      (node (ref "D1") (pin "K") (pinfunction "K_K") (pintype "bidirectional"))
      (node (ref "Q1") (pin "G") (pinfunction "G_G") (pintype "bidirectional"))
      (node (ref "Q2") (pin "D") (pinfunction "D_D") (pintype "bidirectional"))
    )
    (net (code "33") (name "BTN_UP_CAP_2") (class "Default")
      (node (ref "C5") (pin "1") (pinfunction "1_1") (pintype "passive"))
      (node (ref "D5") (pin "K") (pinfunction "K_K") (pintype "bidirectional"))
      (node (ref "Q10") (pin "D") (pinfunction "D_D") (pintype "bidirectional"))
      (node (ref "Q9") (pin "G") (pinfunction "G_G") (pintype "bidirectional"))
    )
    (net (code "34") (name "BTN_UP_CAP_3") (class "Default")
      (node (ref "C7") (pin "1") (pinfunction "1_1") (pintype "passive"))
      (node (ref "D7") (pin "K") (pinfunction "K_K") (pintype "bidirectional"))
      (node (ref "Q13") (pin "G") (pinfunction "G_G") (pintype "bidirectional"))
      (node (ref "Q14") (pin "D") (pinfunction "D_D") (pintype "bidirectional"))
    )
    (net (code "35") (name "BTN_UP_CAP_4") (class "Default")
      (node (ref "C9") (pin "1") (pinfunction "1_1") (pintype "passive"))
      (node (ref "D9") (pin "K") (pinfunction "K_K") (pintype "bidirectional"))
      (node (ref "Q17") (pin "G") (pinfunction "G_G") (pintype "bidirectional"))
      (node (ref "Q18") (pin "D") (pinfunction "D_D") (pintype "bidirectional"))
    )
    (net (code "36") (name "BTN_UP_CAP_5") (class "Default")
      (node (ref "C11") (pin "1") (pinfunction "1_1") (pintype "passive"))
      (node (ref "D11") (pin "K") (pinfunction "K_K") (pintype "bidirectional"))
      (node (ref "Q21") (pin "G") (pinfunction "G_G") (pintype "bidirectional"))
      (node (ref "Q22") (pin "D") (pinfunction "D_D") (pintype "bidirectional"))
    )
    (net (code "37") (name "BTN_UP_CAP_6") (class "Default")
      (node (ref "C15") (pin "1") (pinfunction "1_1") (pintype "passive"))
      (node (ref "D15") (pin "K") (pinfunction "K_K") (pintype "bidirectional"))
      (node (ref "Q29") (pin "G") (pinfunction "G_G") (pintype "bidirectional"))
      (node (ref "Q30") (pin "D") (pinfunction "D_D") (pintype "bidirectional"))
    )
    (net (code "38") (name "BTN_UP_CLR_1") (class "Default")
      (node (ref "JP3") (pin "1") (pinfunction "1_1") (pintype "passive"))
      (node (ref "JP5") (pin "1") (pinfunction "1_1") (pintype "passive"))
      (node (ref "Q2") (pin "G") (pinfunction "G_G") (pintype "bidirectional"))
      (node (ref "R3") (pin "2") (pinfunction "2_2") (pintype "passive"))
    )
    (net (code "39") (name "BTN_UP_CLR_2") (class "Default")
      (node (ref "JP6") (pin "1") (pinfunction "1_1") (pintype "passive"))
      (node (ref "JP8") (pin "1") (pinfunction "1_1") (pintype "passive"))
      (node (ref "Q10") (pin "G") (pinfunction "G_G") (pintype "bidirectional"))
      (node (ref "R15") (pin "2") (pinfunction "2_2") (pintype "passive"))
    )
    (net (code "40") (name "BTN_UP_CLR_3") (class "Default")
      (node (ref "JP10") (pin "1") (pinfunction "1_1") (pintype "passive"))
      (node (ref "JP12") (pin "1") (pinfunction "1_1") (pintype "passive"))
      (node (ref "Q14") (pin "G") (pinfunction "G_G") (pintype "bidirectional"))
      (node (ref "R21") (pin "2") (pinfunction "2_2") (pintype "passive"))
    )
    (net (code "41") (name "BTN_UP_CLR_4") (class "Default")
      (node (ref "JP13") (pin "1") (pinfunction "1_1") (pintype "passive"))
      (node (ref "JP15") (pin "1") (pinfunction "1_1") (pintype "passive"))
      (node (ref "Q18") (pin "G") (pinfunction "G_G") (pintype "bidirectional"))
      (node (ref "R27") (pin "2") (pinfunction "2_2") (pintype "passive"))
    )
    (net (code "42") (name "BTN_UP_CLR_5") (class "Default")
      (node (ref "JP16") (pin "1") (pinfunction "1_1") (pintype "passive"))
      (node (ref "JP18") (pin "1") (pinfunction "1_1") (pintype "passive"))
      (node (ref "Q22") (pin "G") (pinfunction "G_G") (pintype "bidirectional"))
      (node (ref "R33") (pin "2") (pinfunction "2_2") (pintype "passive"))
    )
    (net (code "43") (name "BTN_UP_CLR_6") (class "Default")
      (node (ref "JP19") (pin "1") (pinfunction "1_1") (pintype "passive"))
      (node (ref "JP21") (pin "1") (pinfunction "1_1") (pintype "passive"))
      (node (ref "Q30") (pin "G") (pinfunction "G_G") (pintype "bidirectional"))
      (node (ref "R45") (pin "2") (pinfunction "2_2") (pintype "passive"))
    )
    (net (code "44") (name "BTN_UP_CLR_G") (class "Default")
      (node (ref "JP1") (pin "2") (pinfunction "2_2") (pintype "passive"))
      (node (ref "JP10") (pin "2") (pinfunction "2_2") (pintype "passive"))
      (node (ref "JP13") (pin "2") (pinfunction "2_2") (pintype "passive"))
      (node (ref "JP16") (pin "2") (pinfunction "2_2") (pintype "passive"))
      (node (ref "JP19") (pin "2") (pinfunction "2_2") (pintype "passive"))
      (node (ref "JP2") (pin "2") (pinfunction "2_2") (pintype "passive"))
      (node (ref "JP3") (pin "2") (pinfunction "2_2") (pintype "passive"))
      (node (ref "JP6") (pin "2") (pinfunction "2_2") (pintype "passive"))
    )
    (net (code "45") (name "BTN_UP_SENSE_1") (class "Default")
      (node (ref "JP5") (pin "3") (pinfunction "3_3") (pintype "passive"))
      (node (ref "Q1") (pin "D") (pinfunction "D_D") (pintype "bidirectional"))
      (node (ref "R2") (pin "1") (pinfunction "1_1") (pintype "passive"))
    )
    (net (code "46") (name "BTN_UP_SENSE_2") (class "Default")
      (node (ref "JP8") (pin "3") (pinfunction "3_3") (pintype "passive"))
      (node (ref "Q9") (pin "D") (pinfunction "D_D") (pintype "bidirectional"))
      (node (ref "R14") (pin "1") (pinfunction "1_1") (pintype "passive"))
    )
    (net (code "47") (name "BTN_UP_SENSE_3") (class "Default")
      (node (ref "JP12") (pin "3") (pinfunction "3_3") (pintype "passive"))
      (node (ref "Q13") (pin "D") (pinfunction "D_D") (pintype "bidirectional"))
      (node (ref "R20") (pin "1") (pinfunction "1_1") (pintype "passive"))
    )
    (net (code "48") (name "BTN_UP_SENSE_4") (class "Default")
      (node (ref "JP15") (pin "3") (pinfunction "3_3") (pintype "passive"))
      (node (ref "Q17") (pin "D") (pinfunction "D_D") (pintype "bidirectional"))
      (node (ref "R26") (pin "1") (pinfunction "1_1") (pintype "passive"))
    )
    (net (code "49") (name "BTN_UP_SENSE_5") (class "Default")
      (node (ref "JP18") (pin "3") (pinfunction "3_3") (pintype "passive"))
      (node (ref "Q21") (pin "D") (pinfunction "D_D") (pintype "bidirectional"))
      (node (ref "R32") (pin "1") (pinfunction "1_1") (pintype "passive"))
    )
    (net (code "50") (name "BTN_UP_SENSE_6") (class "Default")
      (node (ref "JP21") (pin "3") (pinfunction "3_3") (pintype "passive"))
      (node (ref "Q29") (pin "D") (pinfunction "D_D") (pintype "bidirectional"))
      (node (ref "R44") (pin "1") (pinfunction "1_1") (pintype "passive"))
    )
    (net (code "51") (name "GND") (class "Default")
      (node (ref "C1") (pin "2") (pinfunction "2_2") (pintype "passive"))
      (node (ref "C10") (pin "2") (pinfunction "2_2") (pintype "passive"))
      (node (ref "C11") (pin "2") (pinfunction "2_2") (pintype "passive"))
      (node (ref "C12") (pin "2") (pinfunction "2_2") (pintype "passive"))
      (node (ref "C15") (pin "2") (pinfunction "2_2") (pintype "passive"))
      (node (ref "C16") (pin "2") (pinfunction "2_2") (pintype "passive"))
      (node (ref "C2") (pin "2") (pinfunction "2_2") (pintype "passive"))
      (node (ref "C3") (pin "2") (pinfunction "2_2") (pintype "passive"))
      (node (ref "C5") (pin "2") (pinfunction "2_2") (pintype "passive"))
      (node (ref "C6") (pin "2") (pinfunction "2_2") (pintype "passive"))
      (node (ref "C7") (pin "2") (pinfunction "2_2") (pintype "passive"))
      (node (ref "C8") (pin "2") (pinfunction "2_2") (pintype "passive"))
      (node (ref "C9") (pin "2") (pinfunction "2_2") (pintype "passive"))
      (node (ref "D3") (pin "A") (pinfunction "A_A") (pintype "passive"))
      (node (ref "JP1") (pin "3") (pinfunction "3_3") (pintype "passive"))
      (node (ref "JP2") (pin "3") (pinfunction "3_3") (pintype "passive"))
      (node (ref "JP9") (pin "1") (pinfunction "1_1") (pintype "bidirectional"))
      (node (ref "JP9") (pin "2") (pinfunction "2_2") (pintype "bidirectional"))
      (node (ref "Q1") (pin "S") (pinfunction "S_S") (pintype "bidirectional"))
      (node (ref "Q10") (pin "S") (pinfunction "S_S") (pintype "bidirectional"))
      (node (ref "Q11") (pin "S") (pinfunction "S_S") (pintype "bidirectional"))
      (node (ref "Q12") (pin "S") (pinfunction "S_S") (pintype "bidirectional"))
      (node (ref "Q13") (pin "S") (pinfunction "S_S") (pintype "bidirectional"))
      (node (ref "Q14") (pin "S") (pinfunction "S_S") (pintype "bidirectional"))
      (node (ref "Q15") (pin "S") (pinfunction "S_S") (pintype "bidirectional"))
      (node (ref "Q16") (pin "S") (pinfunction "S_S") (pintype "bidirectional"))
      (node (ref "Q17") (pin "S") (pinfunction "S_S") (pintype "bidirectional"))
      (node (ref "Q18") (pin "S") (pinfunction "S_S") (pintype "bidirectional"))
      (node (ref "Q19") (pin "S") (pinfunction "S_S") (pintype "bidirectional"))
      (node (ref "Q2") (pin "S") (pinfunction "S_S") (pintype "bidirectional"))
      (node (ref "Q20") (pin "S") (pinfunction "S_S") (pintype "bidirectional"))
      (node (ref "Q21") (pin "S") (pinfunction "S_S") (pintype "bidirectional"))
      (node (ref "Q22") (pin "S") (pinfunction "S_S") (pintype "bidirectional"))
      (node (ref "Q23") (pin "S") (pinfunction "S_S") (pintype "bidirectional"))
      (node (ref "Q24") (pin "S") (pinfunction "S_S") (pintype "bidirectional"))
      (node (ref "Q29") (pin "S") (pinfunction "S_S") (pintype "bidirectional"))
      (node (ref "Q3") (pin "S") (pinfunction "S_S") (pintype "bidirectional"))
      (node (ref "Q30") (pin "S") (pinfunction "S_S") (pintype "bidirectional"))
      (node (ref "Q31") (pin "S") (pinfunction "S_S") (pintype "bidirectional"))
      (node (ref "Q32") (pin "S") (pinfunction "S_S") (pintype "bidirectional"))
      (node (ref "Q4") (pin "S") (pinfunction "S_S") (pintype "bidirectional"))
      (node (ref "Q9") (pin "S") (pinfunction "S_S") (pintype "bidirectional"))
      (node (ref "R1") (pin "1") (pinfunction "1_1") (pintype "passive"))
      (node (ref "R13") (pin "1") (pinfunction "1_1") (pintype "passive"))
      (node (ref "R15") (pin "1") (pinfunction "1_1") (pintype "passive"))
      (node (ref "R16") (pin "1") (pinfunction "1_1") (pintype "passive"))
      (node (ref "R17") (pin "1") (pinfunction "1_1") (pintype "passive"))
      (node (ref "R19") (pin "1") (pinfunction "1_1") (pintype "passive"))
      (node (ref "R21") (pin "1") (pinfunction "1_1") (pintype "passive"))
      (node (ref "R22") (pin "1") (pinfunction "1_1") (pintype "passive"))
      (node (ref "R23") (pin "1") (pinfunction "1_1") (pintype "passive"))
      (node (ref "R25") (pin "1") (pinfunction "1_1") (pintype "passive"))
      (node (ref "R27") (pin "1") (pinfunction "1_1") (pintype "passive"))
      (node (ref "R28") (pin "1") (pinfunction "1_1") (pintype "passive"))
      (node (ref "R29") (pin "1") (pinfunction "1_1") (pintype "passive"))
      (node (ref "R3") (pin "1") (pinfunction "1_1") (pintype "passive"))
      (node (ref "R31") (pin "1") (pinfunction "1_1") (pintype "passive"))
      (node (ref "R33") (pin "1") (pinfunction "1_1") (pintype "passive"))
      (node (ref "R34") (pin "1") (pinfunction "1_1") (pintype "passive"))
      (node (ref "R35") (pin "1") (pinfunction "1_1") (pintype "passive"))
      (node (ref "R4") (pin "1") (pinfunction "1_1") (pintype "passive"))
      (node (ref "R43") (pin "1") (pinfunction "1_1") (pintype "passive"))
      (node (ref "R45") (pin "1") (pinfunction "1_1") (pintype "passive"))
      (node (ref "R46") (pin "1") (pinfunction "1_1") (pintype "passive"))
      (node (ref "R47") (pin "1") (pinfunction "1_1") (pintype "passive"))
      (node (ref "R6") (pin "1") (pinfunction "1_1") (pintype "passive"))
      (node (ref "U1") (pin "P$2") (pinfunction "P$2_P$2") (pintype "bidirectional"))
      (node (ref "U3") (pin "P$2") (pinfunction "P$2_P$2") (pintype "bidirectional"))
      (node (ref "U4") (pin "P$2") (pinfunction "P$2_P$2") (pintype "bidirectional"))
      (node (ref "U5") (pin "P$2") (pinfunction "P$2_P$2") (pintype "bidirectional"))
      (node (ref "U6") (pin "P$2") (pinfunction "P$2_P$2") (pintype "bidirectional"))
      (node (ref "U8") (pin "P$2") (pinfunction "P$2_P$2") (pintype "bidirectional"))
    )
    (net (code "52") (name "HARVEST") (class "Default")
      (node (ref "C3") (pin "1") (pinfunction "1_1") (pintype "passive"))
      (node (ref "D3") (pin "C") (pinfunction "C_C") (pintype "passive"))
      (node (ref "D4") (pin "1") (pinfunction "A_1") (pintype "passive"))
      (node (ref "JP9") (pin "3") (pinfunction "3_3") (pintype "bidirectional"))
      (node (ref "U1") (pin "P$1") (pinfunction "P$1_P$1") (pintype "bidirectional"))
      (node (ref "U3") (pin "P$1") (pinfunction "P$1_P$1") (pintype "bidirectional"))
      (node (ref "U4") (pin "P$1") (pinfunction "P$1_P$1") (pintype "bidirectional"))
      (node (ref "U5") (pin "P$1") (pinfunction "P$1_P$1") (pintype "bidirectional"))
      (node (ref "U6") (pin "P$1") (pinfunction "P$1_P$1") (pintype "bidirectional"))
      (node (ref "U8") (pin "P$1") (pinfunction "P$1_P$1") (pintype "bidirectional"))
    )
    (net (code "53") (name "VCC") (class "Default")
      (node (ref "JP1") (pin "4") (pinfunction "4_4") (pintype "passive"))
      (node (ref "JP2") (pin "4") (pinfunction "4_4") (pintype "passive"))
      (node (ref "R14") (pin "2") (pinfunction "2_2") (pintype "passive"))
      (node (ref "R18") (pin "2") (pinfunction "2_2") (pintype "passive"))
      (node (ref "R2") (pin "2") (pinfunction "2_2") (pintype "passive"))
      (node (ref "R20") (pin "2") (pinfunction "2_2") (pintype "passive"))
      (node (ref "R24") (pin "2") (pinfunction "2_2") (pintype "passive"))
      (node (ref "R26") (pin "2") (pinfunction "2_2") (pintype "passive"))
      (node (ref "R30") (pin "2") (pinfunction "2_2") (pintype "passive"))
      (node (ref "R32") (pin "2") (pinfunction "2_2") (pintype "passive"))
      (node (ref "R36") (pin "2") (pinfunction "2_2") (pintype "passive"))
      (node (ref "R44") (pin "2") (pinfunction "2_2") (pintype "passive"))
      (node (ref "R48") (pin "2") (pinfunction "2_2") (pintype "passive"))
      (node (ref "R5") (pin "2") (pinfunction "2_2") (pintype "passive"))
    )
    (net (code "54") (name "VHARVEST_R") (class "Default")
      (node (ref "D4") (pin "3") (pinfunction "C_3") (pintype "passive"))
      (node (ref "JP9") (pin "4") (pinfunction "4_4") (pintype "bidirectional"))
    )
  )
)
